# SCH-3-ESC1.net
KiCad netlist of a schematic drawn in Altium Designer
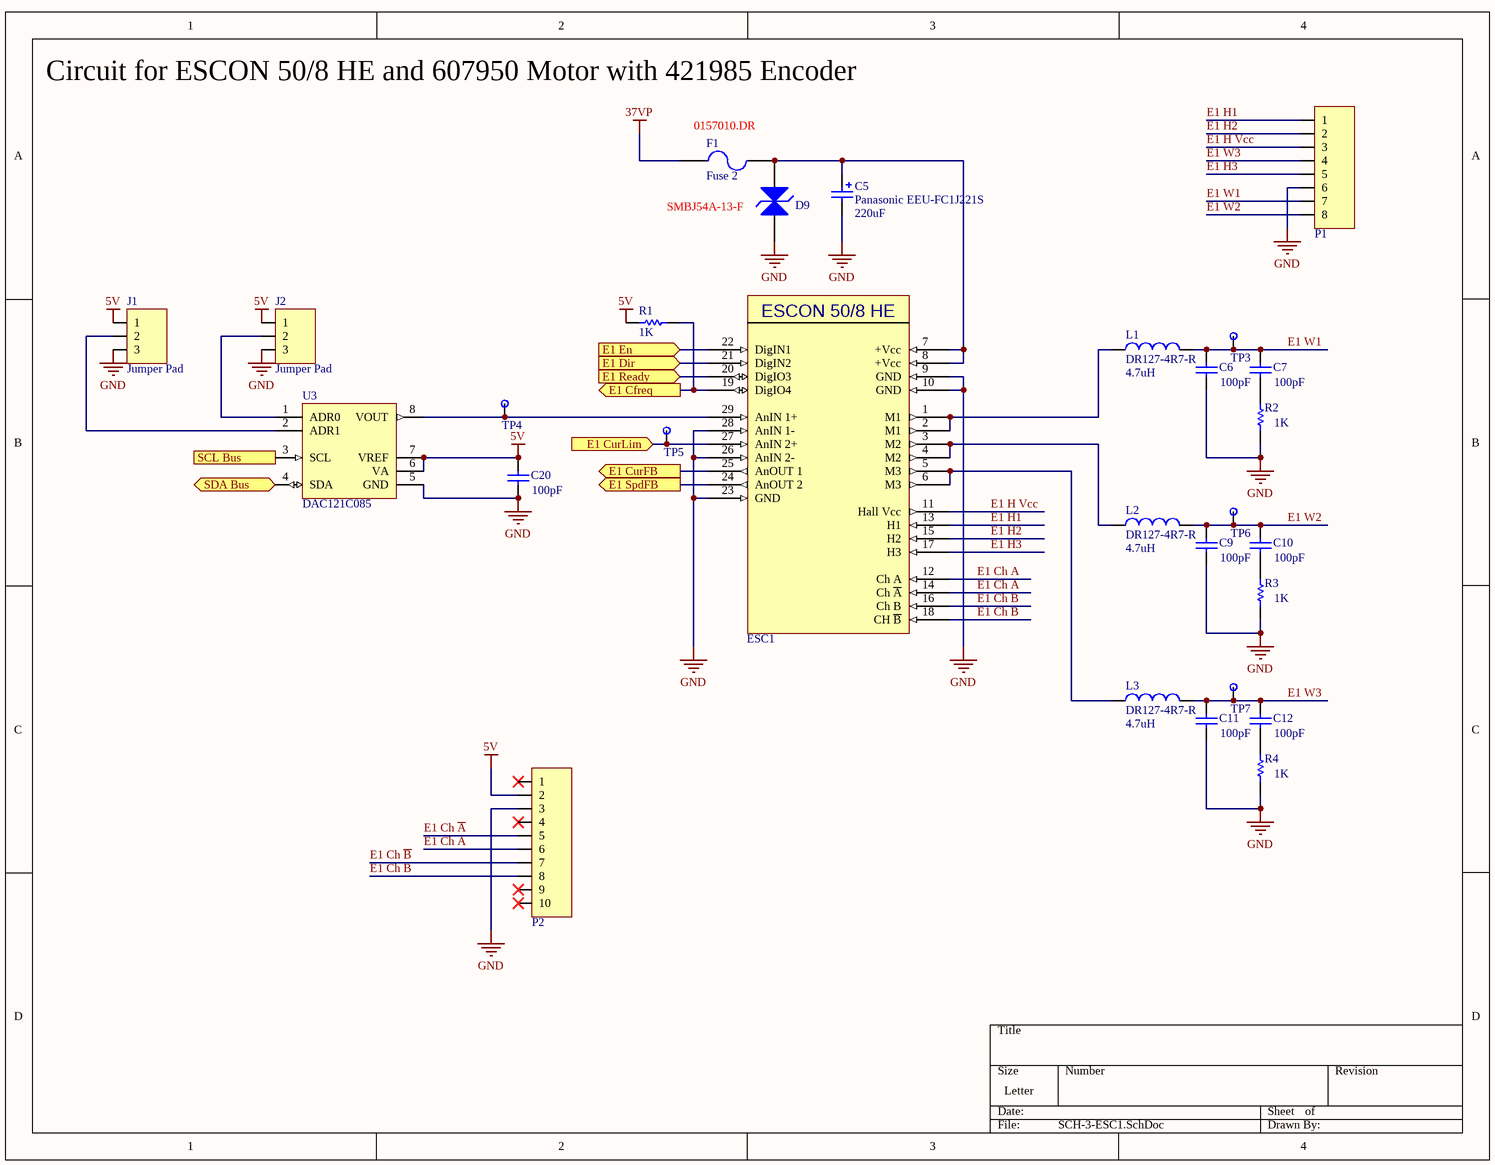
[diagram p0: SCH-3-ESC1.SchDoc]

(export (version "E")
  (design (tool "Eeschema 10.0.6"))
  (components
    (comp (ref "C5")
      (value "Panasonic EEU-FC1J221S")
      (footprint "Panasonic EEU-FC1J221S")
      (description "Polarized Capacitor (Radial)")
      (fields (field (name "ALTIUM_VALUE") "220uF"))
      (libsource (lib "RSX_Capacitors") (part "Panasonic EEU-FC1J221S"))
    )
    (comp (ref "C6")
      (value "100pF")
      (footprint "C1206")
      (description "Capacitor (Semiconductor SIM Model)")
      (fields (field (name "Comment") "Cap Semi") (field (name "PUBLISHER") "Altium Limited"))
      (libsource (lib "Miscellaneous Devices") (part "Cap Semi"))
    )
    (comp (ref "C7")
      (value "100pF")
      (footprint "C1206")
      (description "Capacitor (Semiconductor SIM Model)")
      (fields (field (name "Comment") "Cap Semi") (field (name "PUBLISHER") "Altium Limited"))
      (libsource (lib "Miscellaneous Devices") (part "Cap Semi"))
    )
    (comp (ref "C9")
      (value "100pF")
      (footprint "C1206")
      (description "Capacitor (Semiconductor SIM Model)")
      (fields (field (name "Comment") "Cap Semi") (field (name "PUBLISHER") "Altium Limited"))
      (libsource (lib "Miscellaneous Devices") (part "Cap Semi"))
    )
    (comp (ref "C10")
      (value "100pF")
      (footprint "C1206")
      (description "Capacitor (Semiconductor SIM Model)")
      (fields (field (name "Comment") "Cap Semi") (field (name "PUBLISHER") "Altium Limited"))
      (libsource (lib "Miscellaneous Devices") (part "Cap Semi"))
    )
    (comp (ref "C11")
      (value "100pF")
      (footprint "C1206")
      (description "Capacitor (Semiconductor SIM Model)")
      (fields (field (name "Comment") "Cap Semi") (field (name "PUBLISHER") "Altium Limited"))
      (libsource (lib "Miscellaneous Devices") (part "Cap Semi"))
    )
    (comp (ref "C12")
      (value "100pF")
      (footprint "C1206")
      (description "Capacitor (Semiconductor SIM Model)")
      (fields (field (name "Comment") "Cap Semi") (field (name "PUBLISHER") "Altium Limited"))
      (libsource (lib "Miscellaneous Devices") (part "Cap Semi"))
    )
    (comp (ref "C20")
      (value "100pF")
      (footprint "C1206")
      (description "Capacitor (Semiconductor SIM Model)")
      (fields (field (name "Comment") "Cap Semi") (field (name "PUBLISHER") "Altium Limited"))
      (libsource (lib "Miscellaneous Devices") (part "Cap Semi"))
    )
    (comp (ref "D9")
      (value "TVS_DIODE")
      (footprint "SMBJ54A-13-F")
      (description "TVS Diode")
      (fields (field (name "PUBLISHER") "Altium Limited"))
      (libsource (lib "RSX_Diodes") (part "TVS_DIODE"))
    )
    (comp (ref "ESC1")
      (value "ESCON 50/8 HE")
      (footprint "ESCON 50/8 HE")
      (description "ESCON Module 50/8 HE Servocontroller")
      (libsource (lib "RSX_Modules") (part "ESCON 50/8 HE"))
    )
    (comp (ref "F1")
      (value "Fuse 2")
      (footprint "0157010.DR")
      (description "Fuse")
      (fields (field (name "PUBLISHER") "Altium Limited"))
      (libsource (lib "RSX_Miscellaneous") (part "Fuse 2"))
    )
    (comp (ref "J1")
      (value "Jumper Pad")
      (footprint "3 Pad TH")
      (libsource (lib "RSX_Test_Points") (part "3 Pad Jump Sel"))
    )
    (comp (ref "J2")
      (value "Jumper Pad")
      (footprint "3 Pad TH")
      (libsource (lib "RSX_Test_Points") (part "3 Pad Jump Sel"))
    )
    (comp (ref "L1")
      (value "DR127-4R7-R")
      (footprint "DR127-4R7-R")
      (description "4.7µH Shielded Wirewound Inductor 8.25A 9.17mOhm Nonstandard")
      (fields (field (name "ALTIUM_VALUE") "4.7uH") (field (name "PUBLISHER") "Altium Limited"))
      (libsource (lib "RSX_Inductors") (part "DR127-4R7-R"))
    )
    (comp (ref "L2")
      (value "DR127-4R7-R")
      (footprint "DR127-4R7-R")
      (description "4.7µH Shielded Wirewound Inductor 8.25A 9.17mOhm Nonstandard")
      (fields (field (name "ALTIUM_VALUE") "4.7uH") (field (name "PUBLISHER") "Altium Limited"))
      (libsource (lib "RSX_Inductors") (part "DR127-4R7-R"))
    )
    (comp (ref "L3")
      (value "DR127-4R7-R")
      (footprint "DR127-4R7-R")
      (description "4.7µH Shielded Wirewound Inductor 8.25A 9.17mOhm Nonstandard")
      (fields (field (name "ALTIUM_VALUE") "4.7uH") (field (name "PUBLISHER") "Altium Limited"))
      (libsource (lib "RSX_Inductors") (part "DR127-4R7-R"))
    )
    (comp (ref "P1")
      (value "Mini-Fit Jr 8 Pos")
      (footprint "Molex Mini-Fit Jr 0039281083")
      (libsource (lib "RSX_Connectors") (part "Molex Mini-Fit Jr 8pos Vert"))
    )
    (comp (ref "P2")
      (value "Header_10_Pos_Ribbon Male")
      (footprint "3M_2510-6002UB")
      (description "3M_2510-6002UB")
      (libsource (lib "RSX_Connectors") (part "Header_10_Pos_Ribbon Male"))
    )
    (comp (ref "R1")
      (value "1K")
      (footprint "RESC1608X06N_0603")
      (description "Resistor")
      (fields (field (name "Comment") "Res1") (field (name "PUBLISHER") "Altium Limited"))
      (libsource (lib "RSX_Resistors") (part "Res1"))
    )
    (comp (ref "R2")
      (value "1K")
      (footprint "RESC1608X06N_0603")
      (description "Resistor")
      (fields (field (name "Comment") "Res1") (field (name "PUBLISHER") "Altium Limited"))
      (libsource (lib "RSX_Resistors") (part "Res1"))
    )
    (comp (ref "R3")
      (value "1K")
      (footprint "RESC1608X06N_0603")
      (description "Resistor")
      (fields (field (name "Comment") "Res1") (field (name "PUBLISHER") "Altium Limited"))
      (libsource (lib "RSX_Resistors") (part "Res1"))
    )
    (comp (ref "R4")
      (value "1K")
      (footprint "RESC1608X06N_0603")
      (description "Resistor")
      (fields (field (name "Comment") "Res1") (field (name "PUBLISHER") "Altium Limited"))
      (libsource (lib "RSX_Resistors") (part "Res1"))
    )
    (comp (ref "TP3")
      (value "TestPt")
      (footprint "50_MIL_PAD")
      (libsource (lib "RSX_Test_Points") (part "TestPt"))
    )
    (comp (ref "TP4")
      (value "TestPt")
      (footprint "50_MIL_PAD")
      (libsource (lib "RSX_Test_Points") (part "TestPt"))
    )
    (comp (ref "TP5")
      (value "TestPt")
      (footprint "50_MIL_PAD")
      (libsource (lib "RSX_Test_Points") (part "TestPt"))
    )
    (comp (ref "TP6")
      (value "TestPt")
      (footprint "50_MIL_PAD")
      (libsource (lib "RSX_Test_Points") (part "TestPt"))
    )
    (comp (ref "TP7")
      (value "TestPt")
      (footprint "50_MIL_PAD")
      (libsource (lib "RSX_Test_Points") (part "TestPt"))
    )
    (comp (ref "U3")
      (value "DAC121C085")
      (footprint "MUA08A_L")
      (fields (field (name "MANUFACTURER") "National Semiconductor"))
      (libsource (lib "RSX_Schematics") (part "DAC121C085"))
    )
  )
  (nets
    (net (code "1") (name "/E1 Cfreq") (class "Default")
      (node (ref "ESC1") (pin "19") (pinfunction "DigIO4_19") (pintype "bidirectional"))
      (node (ref "R1") (pin "1") (pinfunction "1_1") (pintype "passive"))
    )
    (net (code "2") (name "/E1 Ch A") (class "Default")
      (node (ref "ESC1") (pin "12") (pinfunction "Ch_A_12") (pintype "input"))
      (node (ref "P2") (pin "6") (pinfunction "6_6") (pintype "passive"))
    )
    (net (code "3") (name "/E1 Ch B") (class "Default")
      (node (ref "ESC1") (pin "16") (pinfunction "Ch_B_16") (pintype "input"))
      (node (ref "P2") (pin "8") (pinfunction "8_8") (pintype "passive"))
    )
    (net (code "4") (name "/E1 Ch ~{A}") (class "Default")
      (node (ref "ESC1") (pin "14") (pinfunction "Ch_~{A}_14") (pintype "input"))
      (node (ref "P2") (pin "5") (pinfunction "5_5") (pintype "passive"))
    )
    (net (code "5") (name "/E1 Ch ~{B}") (class "Default")
      (node (ref "ESC1") (pin "18") (pinfunction "CH_~{B}_18") (pintype "input"))
      (node (ref "P2") (pin "7") (pinfunction "7_7") (pintype "passive"))
    )
    (net (code "6") (name "/E1 CurFB") (class "Default")
      (node (ref "ESC1") (pin "25") (pinfunction "AnOUT_1_25") (pintype "output"))
    )
    (net (code "7") (name "/E1 CurLim") (class "Default")
      (node (ref "ESC1") (pin "27") (pinfunction "AnIN_2+_27") (pintype "input"))
      (node (ref "TP5") (pin "1") (pinfunction "1_1") (pintype "passive"))
    )
    (net (code "8") (name "/E1 Dir") (class "Default")
      (node (ref "ESC1") (pin "21") (pinfunction "DigIN2_21") (pintype "input"))
    )
    (net (code "9") (name "/E1 En") (class "Default")
      (node (ref "ESC1") (pin "22") (pinfunction "DigIN1_22") (pintype "input"))
    )
    (net (code "10") (name "/E1 H Vcc") (class "Default")
      (node (ref "ESC1") (pin "11") (pinfunction "Hall_Vcc_11") (pintype "output"))
      (node (ref "P1") (pin "3") (pinfunction "3_3") (pintype "passive"))
    )
    (net (code "11") (name "/E1 H1") (class "Default")
      (node (ref "ESC1") (pin "13") (pinfunction "H1_13") (pintype "input"))
      (node (ref "P1") (pin "1") (pinfunction "1_1") (pintype "passive"))
    )
    (net (code "12") (name "/E1 H2") (class "Default")
      (node (ref "ESC1") (pin "15") (pinfunction "H2_15") (pintype "input"))
      (node (ref "P1") (pin "2") (pinfunction "2_2") (pintype "passive"))
    )
    (net (code "13") (name "/E1 H3") (class "Default")
      (node (ref "ESC1") (pin "17") (pinfunction "H3_17") (pintype "input"))
      (node (ref "P1") (pin "5") (pinfunction "5_5") (pintype "passive"))
    )
    (net (code "14") (name "/E1 Ready") (class "Default")
      (node (ref "ESC1") (pin "20") (pinfunction "DigIO3_20") (pintype "bidirectional"))
    )
    (net (code "15") (name "/E1 SpdFB") (class "Default")
      (node (ref "ESC1") (pin "24") (pinfunction "AnOUT_2_24") (pintype "output"))
    )
    (net (code "16") (name "/E1 W1") (class "Default")
      (node (ref "C6") (pin "2") (pinfunction "2_2") (pintype "passive"))
      (node (ref "C7") (pin "2") (pinfunction "2_2") (pintype "passive"))
      (node (ref "L1") (pin "2") (pinfunction "2_2") (pintype "passive"))
      (node (ref "P1") (pin "7") (pinfunction "7_7") (pintype "passive"))
      (node (ref "TP3") (pin "1") (pinfunction "1_1") (pintype "passive"))
    )
    (net (code "17") (name "/E1 W2") (class "Default")
      (node (ref "C10") (pin "2") (pinfunction "2_2") (pintype "passive"))
      (node (ref "C9") (pin "2") (pinfunction "2_2") (pintype "passive"))
      (node (ref "L2") (pin "2") (pinfunction "2_2") (pintype "passive"))
      (node (ref "P1") (pin "8") (pinfunction "8_8") (pintype "passive"))
      (node (ref "TP6") (pin "1") (pinfunction "1_1") (pintype "passive"))
    )
    (net (code "18") (name "/E1 W3") (class "Default")
      (node (ref "C11") (pin "2") (pinfunction "2_2") (pintype "passive"))
      (node (ref "C12") (pin "2") (pinfunction "2_2") (pintype "passive"))
      (node (ref "L3") (pin "2") (pinfunction "2_2") (pintype "passive"))
      (node (ref "P1") (pin "4") (pinfunction "4_4") (pintype "passive"))
      (node (ref "TP7") (pin "1") (pinfunction "1_1") (pintype "passive"))
    )
    (net (code "19") (name "/SCL Bus") (class "Default")
      (node (ref "U3") (pin "3") (pinfunction "SCL_3") (pintype "input"))
    )
    (net (code "20") (name "/SDA Bus") (class "Default")
      (node (ref "U3") (pin "4") (pinfunction "SDA_4") (pintype "bidirectional"))
    )
    (net (code "21") (name "5V") (class "Default")
      (node (ref "C20") (pin "2") (pinfunction "2_2") (pintype "passive"))
      (node (ref "J1") (pin "1") (pinfunction "1_1") (pintype "passive"))
      (node (ref "J2") (pin "1") (pinfunction "1_1") (pintype "passive"))
      (node (ref "P2") (pin "2") (pinfunction "2_2") (pintype "passive"))
      (node (ref "R1") (pin "2") (pinfunction "2_2") (pintype "passive"))
      (node (ref "U3") (pin "6") (pinfunction "VA_6") (pintype "power_in"))
      (node (ref "U3") (pin "7") (pinfunction "VREF_7") (pintype "power_in"))
    )
    (net (code "22") (name "37VP") (class "Default")
      (node (ref "F1") (pin "1") (pinfunction "1_1") (pintype "passive"))
    )
    (net (code "23") (name "GND") (class "Default")
      (node (ref "C11") (pin "1") (pinfunction "1_1") (pintype "passive"))
      (node (ref "C20") (pin "1") (pinfunction "1_1") (pintype "passive"))
      (node (ref "C5") (pin "2") (pinfunction "2_2") (pintype "passive"))
      (node (ref "C6") (pin "1") (pinfunction "1_1") (pintype "passive"))
      (node (ref "C9") (pin "1") (pinfunction "1_1") (pintype "passive"))
      (node (ref "D9") (pin "1") (pinfunction "A_1") (pintype "passive"))
      (node (ref "ESC1") (pin "10") (pinfunction "GND_10") (pintype "input"))
      (node (ref "ESC1") (pin "23") (pinfunction "GND_23") (pintype "input"))
      (node (ref "ESC1") (pin "26") (pinfunction "AnIN_2-_26") (pintype "input"))
      (node (ref "ESC1") (pin "28") (pinfunction "AnIN_1-_28") (pintype "input"))
      (node (ref "ESC1") (pin "9") (pinfunction "GND_9") (pintype "input"))
      (node (ref "J1") (pin "3") (pinfunction "3_3") (pintype "passive"))
      (node (ref "J2") (pin "3") (pinfunction "3_3") (pintype "passive"))
      (node (ref "P1") (pin "6") (pinfunction "6_6") (pintype "passive"))
      (node (ref "P2") (pin "3") (pinfunction "3_3") (pintype "passive"))
      (node (ref "R2") (pin "1") (pinfunction "1_1") (pintype "passive"))
      (node (ref "R3") (pin "1") (pinfunction "1_1") (pintype "passive"))
      (node (ref "R4") (pin "1") (pinfunction "1_1") (pintype "passive"))
      (node (ref "U3") (pin "5") (pinfunction "GND_5") (pintype "power_in"))
    )
    (net (code "24") (name "Net-(C7-Pad1)") (class "Default")
      (node (ref "C7") (pin "1") (pinfunction "1_1") (pintype "passive"))
      (node (ref "R2") (pin "2") (pinfunction "2_2") (pintype "passive"))
    )
    (net (code "25") (name "Net-(C10-Pad1)") (class "Default")
      (node (ref "C10") (pin "1") (pinfunction "1_1") (pintype "passive"))
      (node (ref "R3") (pin "2") (pinfunction "2_2") (pintype "passive"))
    )
    (net (code "26") (name "Net-(C12-Pad1)") (class "Default")
      (node (ref "C12") (pin "1") (pinfunction "1_1") (pintype "passive"))
      (node (ref "R4") (pin "2") (pinfunction "2_2") (pintype "passive"))
    )
    (net (code "27") (name "Net-(D9-K)") (class "Default")
      (node (ref "C5") (pin "1") (pinfunction "1_1") (pintype "passive"))
      (node (ref "D9") (pin "2") (pinfunction "K_2") (pintype "passive"))
      (node (ref "ESC1") (pin "7") (pinfunction "+Vcc_7") (pintype "input"))
      (node (ref "ESC1") (pin "8") (pinfunction "+Vcc_8") (pintype "input"))
      (node (ref "F1") (pin "2") (pinfunction "2_2") (pintype "passive"))
    )
    (net (code "28") (name "Net-(ESC1-AnIN_1+)") (class "Default")
      (node (ref "ESC1") (pin "29") (pinfunction "AnIN_1+_29") (pintype "input"))
      (node (ref "TP4") (pin "1") (pinfunction "1_1") (pintype "passive"))
      (node (ref "U3") (pin "8") (pinfunction "VOUT_8") (pintype "output"))
    )
    (net (code "29") (name "Net-(ESC1-M1-Pad1)") (class "Default")
      (node (ref "ESC1") (pin "1") (pinfunction "M1_1") (pintype "output"))
      (node (ref "ESC1") (pin "2") (pinfunction "M1_2") (pintype "output"))
      (node (ref "L1") (pin "1") (pinfunction "1_1") (pintype "passive"))
    )
    (net (code "30") (name "Net-(ESC1-M2-Pad3)") (class "Default")
      (node (ref "ESC1") (pin "3") (pinfunction "M2_3") (pintype "output"))
      (node (ref "ESC1") (pin "4") (pinfunction "M2_4") (pintype "output"))
      (node (ref "L2") (pin "1") (pinfunction "1_1") (pintype "passive"))
    )
    (net (code "31") (name "Net-(ESC1-M3-Pad5)") (class "Default")
      (node (ref "ESC1") (pin "5") (pinfunction "M3_5") (pintype "output"))
      (node (ref "ESC1") (pin "6") (pinfunction "M3_6") (pintype "output"))
      (node (ref "L3") (pin "1") (pinfunction "1_1") (pintype "passive"))
    )
    (net (code "32") (name "Net-(U3-ADR0)") (class "Default")
      (node (ref "J2") (pin "2") (pinfunction "2_2") (pintype "passive"))
      (node (ref "U3") (pin "1") (pinfunction "ADR0_1") (pintype "tri_state"))
    )
    (net (code "33") (name "Net-(U3-ADR1)") (class "Default")
      (node (ref "J1") (pin "2") (pinfunction "2_2") (pintype "passive"))
      (node (ref "U3") (pin "2") (pinfunction "ADR1_2") (pintype "tri_state"))
    )
    (net (code "34") (name "unconnected-(P2-Pad1)") (class "Default")
      (node (ref "P2") (pin "1") (pinfunction "1_1") (pintype "passive+no_connect"))
    )
    (net (code "35") (name "unconnected-(P2-Pad4)") (class "Default")
      (node (ref "P2") (pin "4") (pinfunction "4_4") (pintype "passive+no_connect"))
    )
    (net (code "36") (name "unconnected-(P2-Pad9)") (class "Default")
      (node (ref "P2") (pin "9") (pinfunction "9_9") (pintype "passive+no_connect"))
    )
    (net (code "37") (name "unconnected-(P2-Pad10)") (class "Default")
      (node (ref "P2") (pin "10") (pinfunction "10_10") (pintype "passive+no_connect"))
    )
  )
)
